# module.net
KiCad netlist of a schematic drawn in EAGLE
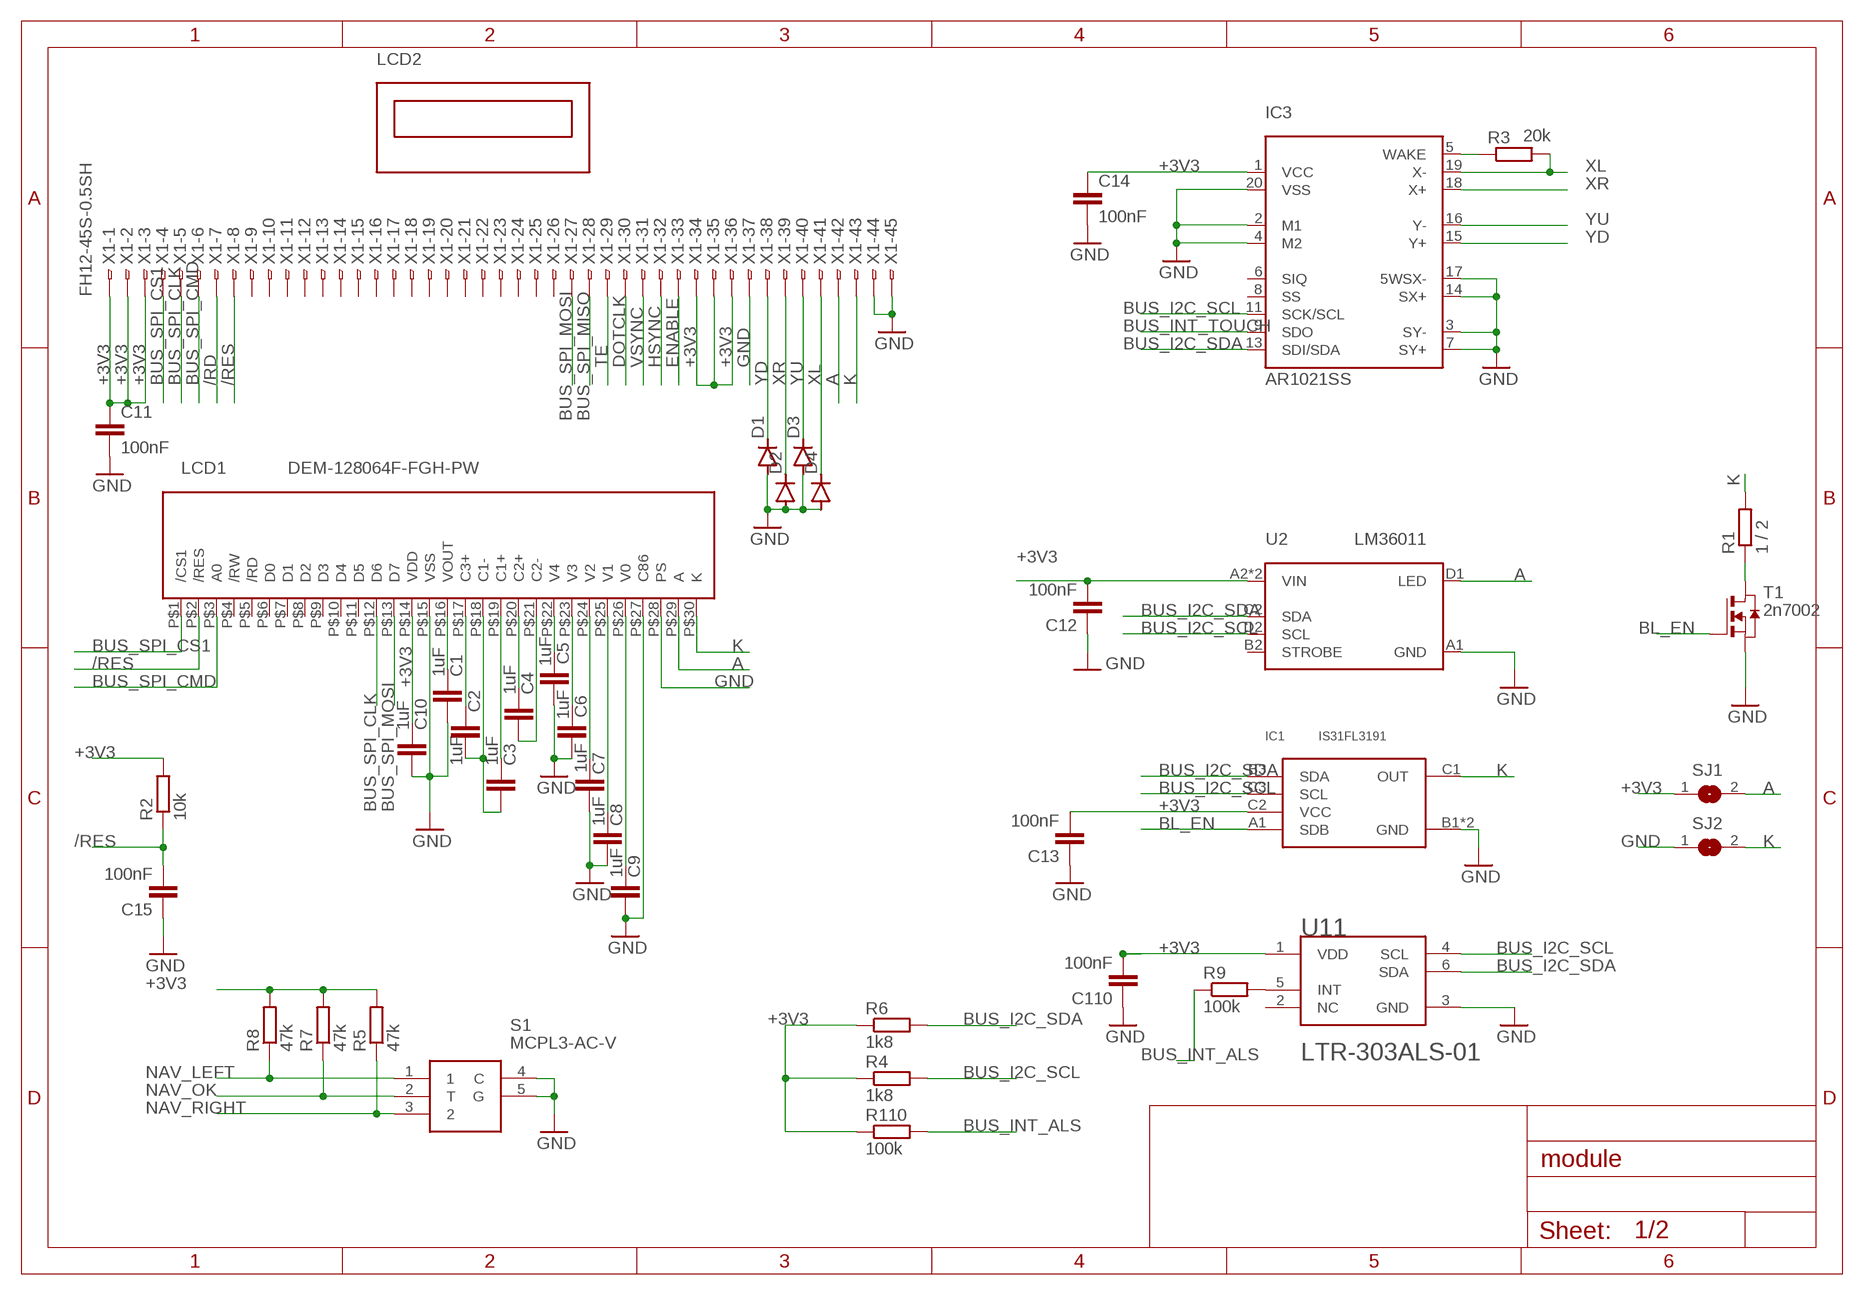
[diagram p0: schematic, sheet 1]
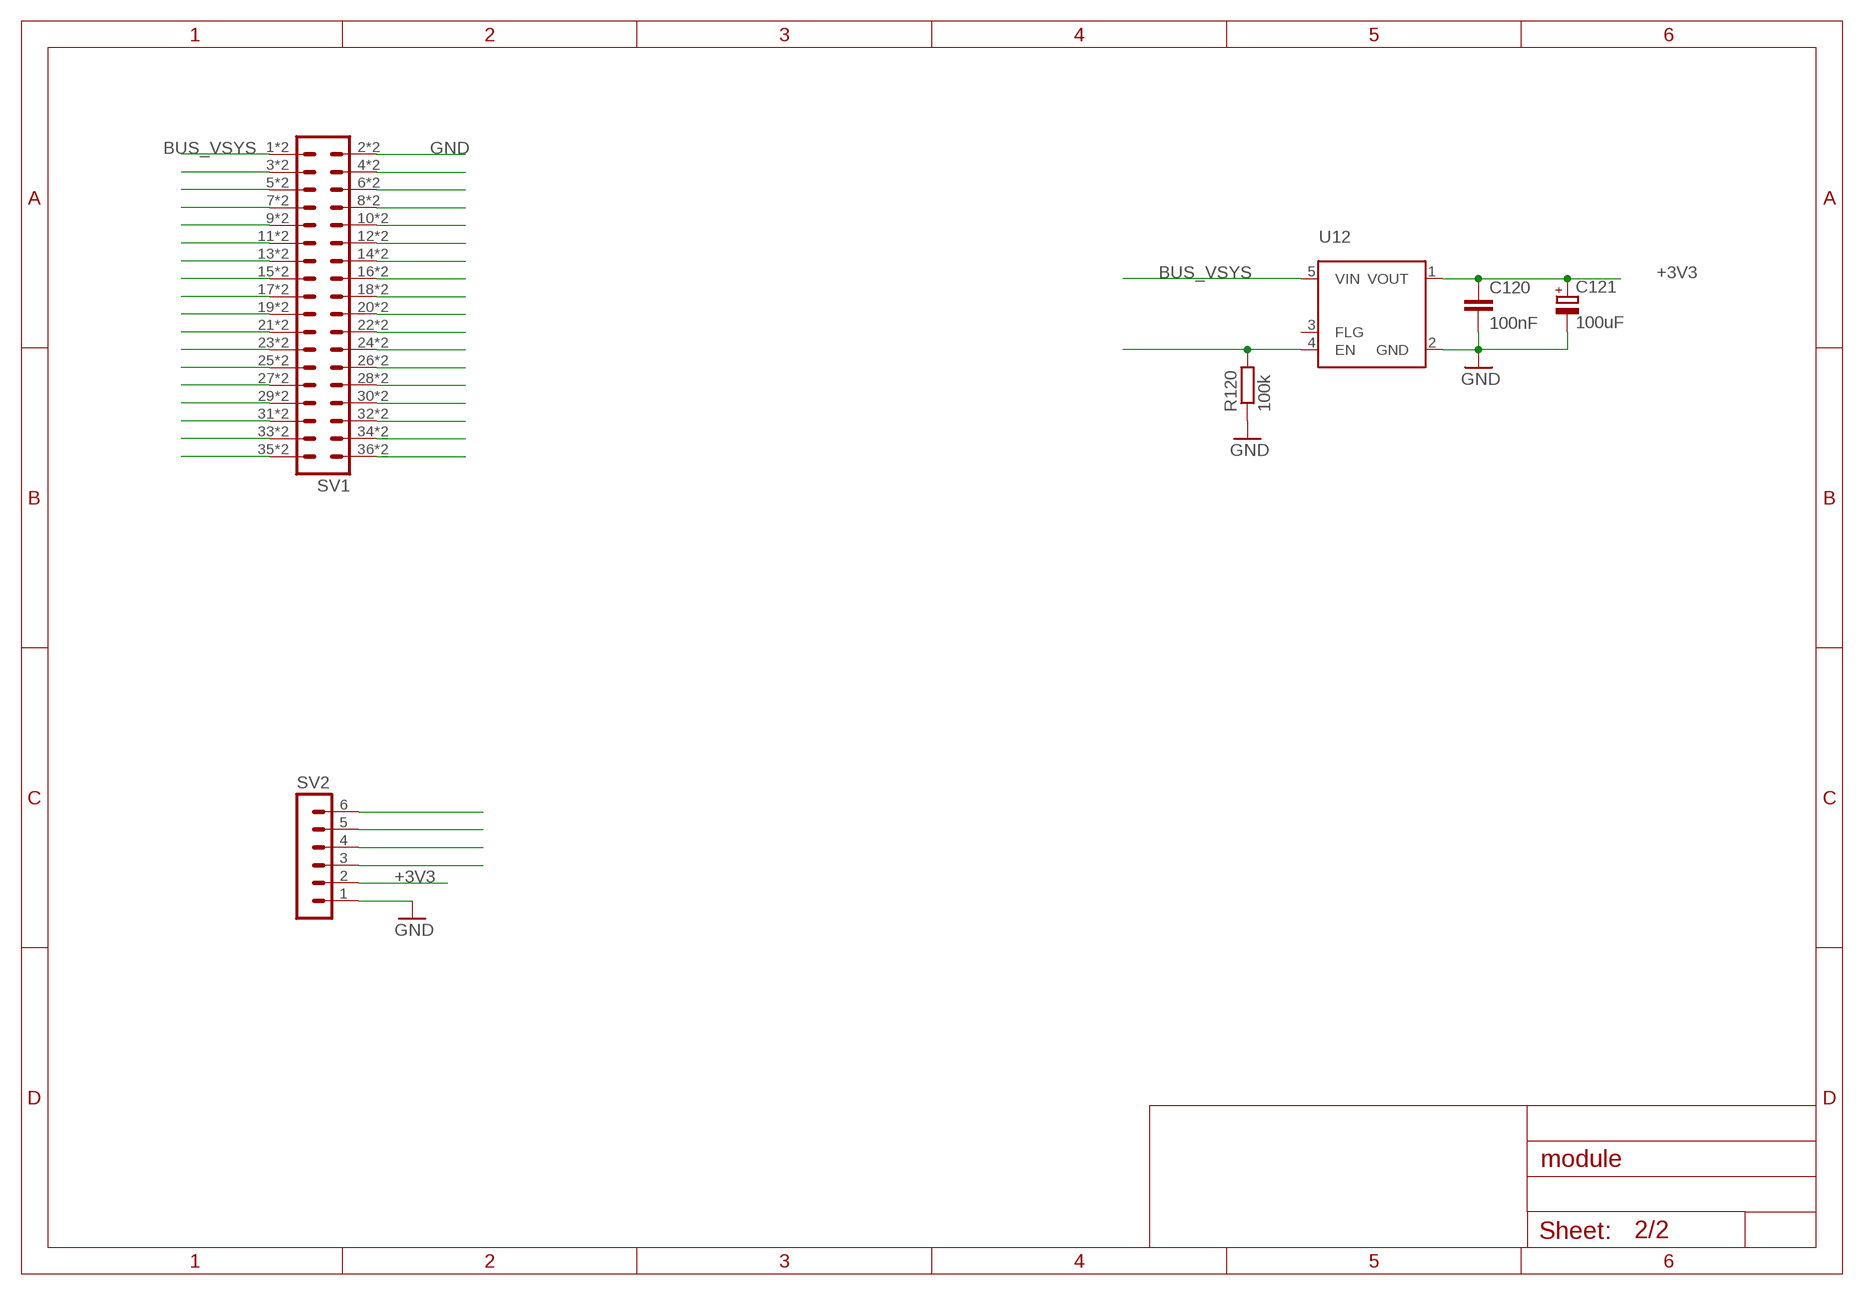
[diagram p1: schematic, sheet 2]

(export (version "E")
  (design (tool "Eeschema 10.0.6"))
  (components
    (comp (ref "C120")
      (value "100nF")
      (footprint "eagle-import:C0402")
      (libsource (lib "eagle-import") (part "C-EUC0402"))
    )
    (comp (ref "C121")
      (value "100uF")
      (footprint "eagle-import:SMC_C")
      (libsource (lib "eagle-import") (part "CPOL-EUSMCC"))
    )
    (comp (ref "R120")
      (value "100k")
      (footprint "eagle-import:R0402")
      (libsource (lib "eagle-import") (part "R-EU_R0402"))
    )
    (comp (ref "SV1")
      (value "MA18-2SMT")
      (footprint "eagle-import:MA18-2-SMT")
      (libsource (lib "eagle-import") (part "MA18-2SMT"))
    )
    (comp (ref "SV2")
      (value "CONN-1X6")
      (footprint "eagle-import:MA06-1")
      (libsource (lib "eagle-import") (part "CONN-1X6"))
    )
    (comp (ref "U12")
      (value "AP22802")
      (footprint "eagle-import:SOT25")
      (libsource (lib "eagle-import") (part "AP22802"))
    )
    (comp (ref "C1")
      (value "1uF")
      (footprint "eagle-import:C0805")
      (libsource (lib "eagle-import") (part "C-EUC0805"))
    )
    (comp (ref "C2")
      (value "1uF")
      (footprint "eagle-import:C0805")
      (libsource (lib "eagle-import") (part "C-EUC0805"))
    )
    (comp (ref "C3")
      (value "1uF")
      (footprint "eagle-import:C0805")
      (libsource (lib "eagle-import") (part "C-EUC0805"))
    )
    (comp (ref "C4")
      (value "1uF")
      (footprint "eagle-import:C0805")
      (libsource (lib "eagle-import") (part "C-EUC0805"))
    )
    (comp (ref "C5")
      (value "1uF")
      (footprint "eagle-import:C0805")
      (libsource (lib "eagle-import") (part "C-EUC0805"))
    )
    (comp (ref "C6")
      (value "1uF")
      (footprint "eagle-import:C0805")
      (libsource (lib "eagle-import") (part "C-EUC0805"))
    )
    (comp (ref "C7")
      (value "1uF")
      (footprint "eagle-import:C0805")
      (libsource (lib "eagle-import") (part "C-EUC0805"))
    )
    (comp (ref "C8")
      (value "1uF")
      (footprint "eagle-import:C0805")
      (libsource (lib "eagle-import") (part "C-EUC0805"))
    )
    (comp (ref "C9")
      (value "1uF")
      (footprint "eagle-import:C0805")
      (libsource (lib "eagle-import") (part "C-EUC0805"))
    )
    (comp (ref "C10")
      (value "1uF")
      (footprint "eagle-import:C0805")
      (libsource (lib "eagle-import") (part "C-EUC0805"))
    )
    (comp (ref "C11")
      (value "100nF")
      (footprint "eagle-import:C0603")
      (libsource (lib "eagle-import") (part "C-EUC0603"))
    )
    (comp (ref "C12")
      (value "100nF")
      (footprint "eagle-import:C0603")
      (libsource (lib "eagle-import") (part "C-EUC0603"))
    )
    (comp (ref "C13")
      (value "100nF")
      (footprint "eagle-import:C0603")
      (libsource (lib "eagle-import") (part "C-EUC0603"))
    )
    (comp (ref "C14")
      (value "100nF")
      (footprint "eagle-import:C0603")
      (libsource (lib "eagle-import") (part "C-EUC0603"))
    )
    (comp (ref "C15")
      (value "100nF")
      (footprint "eagle-import:C0603")
      (libsource (lib "eagle-import") (part "C-EUC0603"))
    )
    (comp (ref "C110")
      (value "100nF")
      (footprint "eagle-import:C0603")
      (libsource (lib "eagle-import") (part "C-EUC0603"))
    )
    (comp (ref "D1")
      (value "DIODE-SOD323-R")
      (footprint "eagle-import:SOD323-R")
      (libsource (lib "eagle-import") (part "DIODE-SOD323-R"))
    )
    (comp (ref "D2")
      (value "DIODE-SOD323-R")
      (footprint "eagle-import:SOD323-R")
      (libsource (lib "eagle-import") (part "DIODE-SOD323-R"))
    )
    (comp (ref "D3")
      (value "DIODE-SOD323-R")
      (footprint "eagle-import:SOD323-R")
      (libsource (lib "eagle-import") (part "DIODE-SOD323-R"))
    )
    (comp (ref "D4")
      (value "DIODE-SOD323-R")
      (footprint "eagle-import:SOD323-R")
      (libsource (lib "eagle-import") (part "DIODE-SOD323-R"))
    )
    (comp (ref "IC1")
      (value "IS31FL3191")
      (footprint "eagle-import:BGA9N40P3X3_133X133X56N")
      (libsource (lib "eagle-import") (part "IS31FL3191"))
    )
    (comp (ref "IC3")
      (value "AR1021SS")
      (footprint "eagle-import:SOP65P780X200-20N")
      (libsource (lib "eagle-import") (part "AR1021SS"))
    )
    (comp (ref "LCD1")
      (value "DEM-128064F-FGH-PW")
      (footprint "eagle-import:DEM128064FFGH")
      (libsource (lib "eagle-import") (part "DEM-128064F-FGH-PW"))
    )
    (comp (ref "LCD2")
      (value "DEM-230320K-TMH-PW")
      (footprint "eagle-import:DEM-240320K-TMH")
      (libsource (lib "eagle-import") (part "DEM-230320K-TMH-PW"))
    )
    (comp (ref "R1")
      (value "1 / 2")
      (footprint "eagle-import:R0603")
      (libsource (lib "eagle-import") (part "R-EU_R0603"))
    )
    (comp (ref "R2")
      (value "10k")
      (footprint "eagle-import:R0603")
      (libsource (lib "eagle-import") (part "R-EU_R0603"))
    )
    (comp (ref "R3")
      (value "20k")
      (footprint "eagle-import:R0603")
      (libsource (lib "eagle-import") (part "R-EU_R0603"))
    )
    (comp (ref "R4")
      (value "1k8")
      (footprint "eagle-import:R0603")
      (libsource (lib "eagle-import") (part "R-EU_R0603"))
    )
    (comp (ref "R5")
      (value "47k")
      (footprint "eagle-import:R0603")
      (libsource (lib "eagle-import") (part "R-EU_R0603"))
    )
    (comp (ref "R6")
      (value "1k8")
      (footprint "eagle-import:R0603")
      (libsource (lib "eagle-import") (part "R-EU_R0603"))
    )
    (comp (ref "R7")
      (value "47k")
      (footprint "eagle-import:R0603")
      (libsource (lib "eagle-import") (part "R-EU_R0603"))
    )
    (comp (ref "R8")
      (value "47k")
      (footprint "eagle-import:R0603")
      (libsource (lib "eagle-import") (part "R-EU_R0603"))
    )
    (comp (ref "R9")
      (value "100k")
      (footprint "eagle-import:R0603")
      (libsource (lib "eagle-import") (part "R-EU_R0603"))
    )
    (comp (ref "R110")
      (value "100k")
      (footprint "eagle-import:R0603")
      (libsource (lib "eagle-import") (part "R-EU_R0603"))
    )
    (comp (ref "S1")
      (value "MCPL3-AC-V")
      (footprint "eagle-import:MCPL3-AC-V")
      (libsource (lib "eagle-import") (part "MCPL3-AC-V"))
    )
    (comp (ref "SJ1") (value "SJ") (footprint "eagle-import:SJ") (libsource (lib "eagle-import") (part "SJ")))
    (comp (ref "SJ2") (value "SJ") (footprint "eagle-import:SJ") (libsource (lib "eagle-import") (part "SJ")))
    (comp (ref "T1")
      (value "2n7002")
      (footprint "eagle-import:SOT-23")
      (libsource (lib "eagle-import") (part "NMOSSOT23"))
    )
    (comp (ref "U2")
      (value "LM36011")
      (footprint "eagle-import:BGA8C35P2X4_151X80X50")
      (libsource (lib "eagle-import") (part "LM36011"))
    )
    (comp (ref "U11")
      (value "LITE-ON_LTR-303ALS-01LITE-ON_LTR-303ALS-01_0_0")
      (footprint "eagle-import:LITE-ON_LTR-303ALS-01_0")
      (fields
        (field (name "DIGIKEY_PART_NUMBER") "160-2161-1-ND")
        (field (name "MF") "Lite-On")
        (field (name "MOUSER_PART_NUMBER") "859-LTR-303ALS-01")
      )
      (libsource (lib "eagle-import") (part "LITE-ON_LTR-303ALS-01LITE-ON_LTR-303ALS-01_0_0"))
    )
    (comp (ref "X1")
      (value "FH12-45S-0.5SH")
      (footprint "eagle-import:FH12-45S-0.5SH")
      (libsource (lib "eagle-import") (part "FH12-45S-0.5SH"))
    )
  )
  (nets
    (net (code "1") (name "+3V3") (class "Default")
      (node (ref "C10") (pin "1") (pinfunction "1_1") (pintype "passive"))
      (node (ref "C11") (pin "1") (pinfunction "1_1") (pintype "passive"))
      (node (ref "C110") (pin "2") (pinfunction "2_2") (pintype "passive"))
      (node (ref "C12") (pin "2") (pinfunction "2_2") (pintype "passive"))
      (node (ref "C120") (pin "1") (pinfunction "1_1") (pintype "passive"))
      (node (ref "C121") (pin "+") (pinfunction "+_+") (pintype "passive"))
      (node (ref "C13") (pin "2") (pinfunction "2_2") (pintype "passive"))
      (node (ref "C14") (pin "1") (pinfunction "1_1") (pintype "passive"))
      (node (ref "IC1") (pin "C2") (pinfunction "VCC_C2") (pintype "bidirectional"))
      (node (ref "IC3") (pin "1") (pinfunction "VCC_1") (pintype "bidirectional"))
      (node (ref "LCD1") (pin "P$14") (pinfunction "VDD_P$14") (pintype "bidirectional"))
      (node (ref "R110") (pin "1") (pinfunction "1_1") (pintype "passive"))
      (node (ref "R2") (pin "2") (pinfunction "2_2") (pintype "passive"))
      (node (ref "R4") (pin "1") (pinfunction "1_1") (pintype "passive"))
      (node (ref "R5") (pin "2") (pinfunction "2_2") (pintype "passive"))
      (node (ref "R6") (pin "1") (pinfunction "1_1") (pintype "passive"))
      (node (ref "R7") (pin "2") (pinfunction "2_2") (pintype "passive"))
      (node (ref "R8") (pin "2") (pinfunction "2_2") (pintype "passive"))
      (node (ref "SJ1") (pin "1") (pinfunction "1_1") (pintype "passive"))
      (node (ref "SV2") (pin "2") (pinfunction "2_2") (pintype "passive"))
      (node (ref "U11") (pin "1") (pinfunction "VDD_1") (pintype "bidirectional"))
      (node (ref "U12") (pin "1") (pinfunction "VOUT_1") (pintype "bidirectional"))
      (node (ref "U2") (pin "A2") (pinfunction "VIN_A2") (pintype "bidirectional"))
      (node (ref "U2") (pin "C1") (pinfunction "VIN_C1") (pintype "bidirectional"))
      (node (ref "X1") (pin "1") (pinfunction "1_1") (pintype "passive"))
      (node (ref "X1") (pin "2") (pinfunction "1_2") (pintype "passive"))
      (node (ref "X1") (pin "3") (pinfunction "1_3") (pintype "passive"))
      (node (ref "X1") (pin "34") (pinfunction "1_34") (pintype "passive"))
      (node (ref "X1") (pin "35") (pinfunction "1_35") (pintype "passive"))
      (node (ref "X1") (pin "36") (pinfunction "1_36") (pintype "passive"))
    )
    (net (code "2") (name "A") (class "Default")
      (node (ref "LCD1") (pin "P$29") (pinfunction "A_P$29") (pintype "bidirectional"))
      (node (ref "SJ1") (pin "2") (pinfunction "2_2") (pintype "passive"))
      (node (ref "U2") (pin "D1") (pinfunction "LED_D1") (pintype "bidirectional"))
      (node (ref "X1") (pin "42") (pinfunction "1_42") (pintype "passive"))
    )
    (net (code "3") (name "BL_EN") (class "Default")
      (node (ref "IC1") (pin "A1") (pinfunction "SDB_A1") (pintype "bidirectional"))
      (node (ref "T1") (pin "3") (pinfunction "G_3") (pintype "passive"))
    )
    (net (code "4") (name "BUS_I2C_SCL") (class "Default")
      (node (ref "IC1") (pin "C3") (pinfunction "SCL_C3") (pintype "bidirectional"))
      (node (ref "IC3") (pin "11") (pinfunction "SCK/SCL_11") (pintype "bidirectional"))
      (node (ref "R4") (pin "2") (pinfunction "2_2") (pintype "passive"))
      (node (ref "U11") (pin "4") (pinfunction "SCL_4") (pintype "bidirectional"))
      (node (ref "U2") (pin "D2") (pinfunction "SCL_D2") (pintype "bidirectional"))
    )
    (net (code "5") (name "BUS_I2C_SDA") (class "Default")
      (node (ref "IC1") (pin "B3") (pinfunction "SDA_B3") (pintype "bidirectional"))
      (node (ref "IC3") (pin "13") (pinfunction "SDI/SDA_13") (pintype "bidirectional"))
      (node (ref "R6") (pin "2") (pinfunction "2_2") (pintype "passive"))
      (node (ref "U11") (pin "6") (pinfunction "SDA_6") (pintype "bidirectional"))
      (node (ref "U2") (pin "C2") (pinfunction "SDA_C2") (pintype "bidirectional"))
    )
    (net (code "6") (name "BUS_INT_ALS") (class "Default")
      (node (ref "R110") (pin "2") (pinfunction "2_2") (pintype "passive"))
      (node (ref "R9") (pin "1") (pinfunction "1_1") (pintype "passive"))
    )
    (net (code "7") (name "BUS_INT_TOUCH") (class "Default")
      (node (ref "IC3") (pin "9") (pinfunction "SDO_9") (pintype "bidirectional"))
    )
    (net (code "8") (name "BUS_SPI_CLK") (class "Default")
      (node (ref "LCD1") (pin "P$12") (pinfunction "D6_P$12") (pintype "bidirectional"))
      (node (ref "X1") (pin "5") (pinfunction "1_5") (pintype "passive"))
    )
    (net (code "9") (name "BUS_SPI_CMD") (class "Default")
      (node (ref "LCD1") (pin "P$3") (pinfunction "A0_P$3") (pintype "bidirectional"))
      (node (ref "X1") (pin "6") (pinfunction "1_6") (pintype "passive"))
    )
    (net (code "10") (name "BUS_SPI_CS1") (class "Default")
      (node (ref "LCD1") (pin "P$1") (pinfunction "/CS1_P$1") (pintype "bidirectional"))
      (node (ref "X1") (pin "4") (pinfunction "1_4") (pintype "passive"))
    )
    (net (code "11") (name "BUS_SPI_MISO") (class "Default")
      (node (ref "X1") (pin "28") (pinfunction "1_28") (pintype "passive"))
    )
    (net (code "12") (name "BUS_SPI_MOSI") (class "Default")
      (node (ref "LCD1") (pin "P$13") (pinfunction "D7_P$13") (pintype "bidirectional"))
      (node (ref "X1") (pin "27") (pinfunction "1_27") (pintype "passive"))
    )
    (net (code "13") (name "BUS_VSYS") (class "Default")
      (node (ref "SV1") (pin "1") (pinfunction "1_1") (pintype "passive"))
      (node (ref "SV1") (pin "P$1") (pinfunction "1_P$1") (pintype "passive"))
      (node (ref "U12") (pin "5") (pinfunction "VIN_5") (pintype "bidirectional"))
    )
    (net (code "14") (name "DOTCLK") (class "Default")
      (node (ref "X1") (pin "30") (pinfunction "1_30") (pintype "passive"))
    )
    (net (code "15") (name "ENABLE") (class "Default")
      (node (ref "X1") (pin "33") (pinfunction "1_33") (pintype "passive"))
    )
    (net (code "16") (name "GND") (class "Default")
      (node (ref "C1") (pin "2") (pinfunction "2_2") (pintype "passive"))
      (node (ref "C10") (pin "2") (pinfunction "2_2") (pintype "passive"))
      (node (ref "C11") (pin "2") (pinfunction "2_2") (pintype "passive"))
      (node (ref "C110") (pin "1") (pinfunction "1_1") (pintype "passive"))
      (node (ref "C12") (pin "1") (pinfunction "1_1") (pintype "passive"))
      (node (ref "C120") (pin "2") (pinfunction "2_2") (pintype "passive"))
      (node (ref "C121") (pin "-") (pinfunction "-_-") (pintype "passive"))
      (node (ref "C13") (pin "1") (pinfunction "1_1") (pintype "passive"))
      (node (ref "C14") (pin "2") (pinfunction "2_2") (pintype "passive"))
      (node (ref "C15") (pin "1") (pinfunction "1_1") (pintype "passive"))
      (node (ref "C5") (pin "2") (pinfunction "2_2") (pintype "passive"))
      (node (ref "C6") (pin "2") (pinfunction "2_2") (pintype "passive"))
      (node (ref "C7") (pin "2") (pinfunction "2_2") (pintype "passive"))
      (node (ref "C8") (pin "2") (pinfunction "2_2") (pintype "passive"))
      (node (ref "C9") (pin "2") (pinfunction "2_2") (pintype "passive"))
      (node (ref "D1") (pin "A") (pinfunction "A_A") (pintype "passive"))
      (node (ref "D2") (pin "A") (pinfunction "A_A") (pintype "passive"))
      (node (ref "D3") (pin "A") (pinfunction "A_A") (pintype "passive"))
      (node (ref "D4") (pin "A") (pinfunction "A_A") (pintype "passive"))
      (node (ref "IC1") (pin "B1") (pinfunction "GND_B1") (pintype "bidirectional"))
      (node (ref "IC1") (pin "B2") (pinfunction "GND_B2") (pintype "bidirectional"))
      (node (ref "IC3") (pin "14") (pinfunction "SX+_14") (pintype "bidirectional"))
      (node (ref "IC3") (pin "17") (pinfunction "5WSX-_17") (pintype "bidirectional"))
      (node (ref "IC3") (pin "2") (pinfunction "M1_2") (pintype "bidirectional"))
      (node (ref "IC3") (pin "20") (pinfunction "VSS_20") (pintype "bidirectional"))
      (node (ref "IC3") (pin "3") (pinfunction "SY-_3") (pintype "bidirectional"))
      (node (ref "IC3") (pin "4") (pinfunction "M2_4") (pintype "bidirectional"))
      (node (ref "IC3") (pin "7") (pinfunction "SY+_7") (pintype "bidirectional"))
      (node (ref "LCD1") (pin "P$15") (pinfunction "VSS_P$15") (pintype "bidirectional"))
      (node (ref "LCD1") (pin "P$27") (pinfunction "C86_P$27") (pintype "bidirectional"))
      (node (ref "LCD1") (pin "P$28") (pinfunction "PS_P$28") (pintype "bidirectional"))
      (node (ref "R120") (pin "1") (pinfunction "1_1") (pintype "passive"))
      (node (ref "S1") (pin "4") (pinfunction "C_4") (pintype "bidirectional"))
      (node (ref "S1") (pin "5") (pinfunction "G_5") (pintype "bidirectional"))
      (node (ref "SJ2") (pin "1") (pinfunction "1_1") (pintype "passive"))
      (node (ref "SV1") (pin "2") (pinfunction "2_2") (pintype "passive"))
      (node (ref "SV1") (pin "P$2") (pinfunction "2_P$2") (pintype "passive"))
      (node (ref "SV2") (pin "1") (pinfunction "1_1") (pintype "passive"))
      (node (ref "T1") (pin "2") (pinfunction "S_2") (pintype "passive"))
      (node (ref "U11") (pin "3") (pinfunction "GND_3") (pintype "bidirectional"))
      (node (ref "U12") (pin "2") (pinfunction "GND_2") (pintype "bidirectional"))
      (node (ref "U2") (pin "A1") (pinfunction "GND_A1") (pintype "bidirectional"))
      (node (ref "X1") (pin "37") (pinfunction "1_37") (pintype "passive"))
      (node (ref "X1") (pin "44") (pinfunction "1_44") (pintype "passive"))
      (node (ref "X1") (pin "45") (pinfunction "1_45") (pintype "passive"))
    )
    (net (code "17") (name "HSYNC") (class "Default")
      (node (ref "X1") (pin "32") (pinfunction "1_32") (pintype "passive"))
    )
    (net (code "18") (name "K") (class "Default")
      (node (ref "IC1") (pin "C1") (pinfunction "OUT_C1") (pintype "bidirectional"))
      (node (ref "LCD1") (pin "P$30") (pinfunction "K_P$30") (pintype "bidirectional"))
      (node (ref "R1") (pin "2") (pinfunction "2_2") (pintype "passive"))
      (node (ref "SJ2") (pin "2") (pinfunction "2_2") (pintype "passive"))
      (node (ref "X1") (pin "43") (pinfunction "1_43") (pintype "passive"))
    )
    (net (code "19") (name "NAV_LEFT") (class "Default")
      (node (ref "R8") (pin "1") (pinfunction "1_1") (pintype "passive"))
      (node (ref "S1") (pin "1") (pinfunction "1_1") (pintype "bidirectional"))
    )
    (net (code "20") (name "NAV_OK") (class "Default")
      (node (ref "R7") (pin "1") (pinfunction "1_1") (pintype "passive"))
      (node (ref "S1") (pin "2") (pinfunction "T_2") (pintype "bidirectional"))
    )
    (net (code "21") (name "NAV_RIGHT") (class "Default")
      (node (ref "R5") (pin "1") (pinfunction "1_1") (pintype "passive"))
      (node (ref "S1") (pin "3") (pinfunction "2_3") (pintype "bidirectional"))
    )
    (net (code "22") (name "Net-(IC3-WAKE)") (class "Default")
      (node (ref "IC3") (pin "5") (pinfunction "WAKE_5") (pintype "bidirectional"))
      (node (ref "R3") (pin "1") (pinfunction "1_1") (pintype "passive"))
    )
    (net (code "23") (name "Net-(LCD1-C1+)") (class "Default")
      (node (ref "C3") (pin "1") (pinfunction "1_1") (pintype "passive"))
      (node (ref "LCD1") (pin "P$19") (pinfunction "C1+_P$19") (pintype "bidirectional"))
    )
    (net (code "24") (name "Net-(LCD1-C1-)") (class "Default")
      (node (ref "C2") (pin "2") (pinfunction "2_2") (pintype "passive"))
      (node (ref "C3") (pin "2") (pinfunction "2_2") (pintype "passive"))
      (node (ref "LCD1") (pin "P$18") (pinfunction "C1-_P$18") (pintype "bidirectional"))
    )
    (net (code "25") (name "Net-(LCD1-C2+)") (class "Default")
      (node (ref "C4") (pin "1") (pinfunction "1_1") (pintype "passive"))
      (node (ref "LCD1") (pin "P$20") (pinfunction "C2+_P$20") (pintype "bidirectional"))
    )
    (net (code "26") (name "Net-(LCD1-C2-)") (class "Default")
      (node (ref "C4") (pin "2") (pinfunction "2_2") (pintype "passive"))
      (node (ref "LCD1") (pin "P$21") (pinfunction "C2-_P$21") (pintype "bidirectional"))
    )
    (net (code "27") (name "Net-(LCD1-C3+)") (class "Default")
      (node (ref "C2") (pin "1") (pinfunction "1_1") (pintype "passive"))
      (node (ref "LCD1") (pin "P$17") (pinfunction "C3+_P$17") (pintype "bidirectional"))
    )
    (net (code "28") (name "Net-(LCD1-V0)") (class "Default")
      (node (ref "C9") (pin "1") (pinfunction "1_1") (pintype "passive"))
      (node (ref "LCD1") (pin "P$26") (pinfunction "V0_P$26") (pintype "bidirectional"))
    )
    (net (code "29") (name "Net-(LCD1-V1)") (class "Default")
      (node (ref "C8") (pin "1") (pinfunction "1_1") (pintype "passive"))
      (node (ref "LCD1") (pin "P$25") (pinfunction "V1_P$25") (pintype "bidirectional"))
    )
    (net (code "30") (name "Net-(LCD1-V2)") (class "Default")
      (node (ref "C7") (pin "1") (pinfunction "1_1") (pintype "passive"))
      (node (ref "LCD1") (pin "P$24") (pinfunction "V2_P$24") (pintype "bidirectional"))
    )
    (net (code "31") (name "Net-(LCD1-V3)") (class "Default")
      (node (ref "C6") (pin "1") (pinfunction "1_1") (pintype "passive"))
      (node (ref "LCD1") (pin "P$23") (pinfunction "V3_P$23") (pintype "bidirectional"))
    )
    (net (code "32") (name "Net-(LCD1-V4)") (class "Default")
      (node (ref "C5") (pin "1") (pinfunction "1_1") (pintype "passive"))
      (node (ref "LCD1") (pin "P$22") (pinfunction "V4_P$22") (pintype "bidirectional"))
    )
    (net (code "33") (name "Net-(LCD1-VOUT)") (class "Default")
      (node (ref "C1") (pin "1") (pinfunction "1_1") (pintype "passive"))
      (node (ref "LCD1") (pin "P$16") (pinfunction "VOUT_P$16") (pintype "bidirectional"))
    )
    (net (code "34") (name "Net-(SV1-3-PadP$3)") (class "Default")
      (node (ref "SV1") (pin "3") (pinfunction "3_3") (pintype "passive"))
      (node (ref "SV1") (pin "P$3") (pinfunction "3_P$3") (pintype "passive"))
    )
    (net (code "35") (name "Net-(SV1-4-PadP$4)") (class "Default")
      (node (ref "SV1") (pin "4") (pinfunction "4_4") (pintype "passive"))
      (node (ref "SV1") (pin "P$4") (pinfunction "4_P$4") (pintype "passive"))
    )
    (net (code "36") (name "Net-(SV1-5-PadP$5)") (class "Default")
      (node (ref "SV1") (pin "5") (pinfunction "5_5") (pintype "passive"))
      (node (ref "SV1") (pin "P$5") (pinfunction "5_P$5") (pintype "passive"))
    )
    (net (code "37") (name "Net-(SV1-6-PadP$6)") (class "Default")
      (node (ref "SV1") (pin "6") (pinfunction "6_6") (pintype "passive"))
      (node (ref "SV1") (pin "P$6") (pinfunction "6_P$6") (pintype "passive"))
    )
    (net (code "38") (name "Net-(SV1-7-PadP$7)") (class "Default")
      (node (ref "SV1") (pin "7") (pinfunction "7_7") (pintype "passive"))
      (node (ref "SV1") (pin "P$7") (pinfunction "7_P$7") (pintype "passive"))
    )
    (net (code "39") (name "Net-(SV1-8-PadP$8)") (class "Default")
      (node (ref "SV1") (pin "8") (pinfunction "8_8") (pintype "passive"))
      (node (ref "SV1") (pin "P$8") (pinfunction "8_P$8") (pintype "passive"))
    )
    (net (code "40") (name "Net-(SV1-9-PadP$9)") (class "Default")
      (node (ref "SV1") (pin "9") (pinfunction "9_9") (pintype "passive"))
      (node (ref "SV1") (pin "P$9") (pinfunction "9_P$9") (pintype "passive"))
    )
    (net (code "41") (name "Net-(SV1-10-PadP$10)") (class "Default")
      (node (ref "SV1") (pin "10") (pinfunction "10_10") (pintype "passive"))
      (node (ref "SV1") (pin "P$10") (pinfunction "10_P$10") (pintype "passive"))
    )
    (net (code "42") (name "Net-(SV1-11-PadP$11)") (class "Default")
      (node (ref "SV1") (pin "11") (pinfunction "11_11") (pintype "passive"))
      (node (ref "SV1") (pin "P$11") (pinfunction "11_P$11") (pintype "passive"))
    )
    (net (code "43") (name "Net-(SV1-12-PadP$12)") (class "Default")
      (node (ref "SV1") (pin "12") (pinfunction "12_12") (pintype "passive"))
      (node (ref "SV1") (pin "P$12") (pinfunction "12_P$12") (pintype "passive"))
    )
    (net (code "44") (name "Net-(SV1-13-PadP$13)") (class "Default")
      (node (ref "SV1") (pin "13") (pinfunction "13_13") (pintype "passive"))
      (node (ref "SV1") (pin "P$13") (pinfunction "13_P$13") (pintype "passive"))
    )
    (net (code "45") (name "Net-(SV1-14-PadP$14)") (class "Default")
      (node (ref "SV1") (pin "14") (pinfunction "14_14") (pintype "passive"))
      (node (ref "SV1") (pin "P$14") (pinfunction "14_P$14") (pintype "passive"))
    )
    (net (code "46") (name "Net-(SV1-15-PadP$15)") (class "Default")
      (node (ref "SV1") (pin "15") (pinfunction "15_15") (pintype "passive"))
      (node (ref "SV1") (pin "P$15") (pinfunction "15_P$15") (pintype "passive"))
    )
    (net (code "47") (name "Net-(SV1-16-PadP$16)") (class "Default")
      (node (ref "SV1") (pin "16") (pinfunction "16_16") (pintype "passive"))
      (node (ref "SV1") (pin "P$16") (pinfunction "16_P$16") (pintype "passive"))
    )
    (net (code "48") (name "Net-(SV1-17-PadP$17)") (class "Default")
      (node (ref "SV1") (pin "17") (pinfunction "17_17") (pintype "passive"))
      (node (ref "SV1") (pin "P$17") (pinfunction "17_P$17") (pintype "passive"))
    )
    (net (code "49") (name "Net-(SV1-18-PadP$18)") (class "Default")
      (node (ref "SV1") (pin "18") (pinfunction "18_18") (pintype "passive"))
      (node (ref "SV1") (pin "P$18") (pinfunction "18_P$18") (pintype "passive"))
    )
    (net (code "50") (name "Net-(SV1-19-PadP$19)") (class "Default")
      (node (ref "SV1") (pin "19") (pinfunction "19_19") (pintype "passive"))
      (node (ref "SV1") (pin "P$19") (pinfunction "19_P$19") (pintype "passive"))
    )
    (net (code "51") (name "Net-(SV1-20-PadP$20)") (class "Default")
      (node (ref "SV1") (pin "20") (pinfunction "20_20") (pintype "passive"))
      (node (ref "SV1") (pin "P$20") (pinfunction "20_P$20") (pintype "passive"))
    )
    (net (code "52") (name "Net-(SV1-21-PadP$21)") (class "Default")
      (node (ref "SV1") (pin "21") (pinfunction "21_21") (pintype "passive"))
      (node (ref "SV1") (pin "P$21") (pinfunction "21_P$21") (pintype "passive"))
    )
    (net (code "53") (name "Net-(SV1-22-PadP$22)") (class "Default")
      (node (ref "SV1") (pin "22") (pinfunction "22_22") (pintype "passive"))
      (node (ref "SV1") (pin "P$22") (pinfunction "22_P$22") (pintype "passive"))
    )
    (net (code "54") (name "Net-(SV1-23-PadP$23)") (class "Default")
      (node (ref "SV1") (pin "23") (pinfunction "23_23") (pintype "passive"))
      (node (ref "SV1") (pin "P$23") (pinfunction "23_P$23") (pintype "passive"))
    )
    (net (code "55") (name "Net-(SV1-24-PadP$24)") (class "Default")
      (node (ref "SV1") (pin "24") (pinfunction "24_24") (pintype "passive"))
      (node (ref "SV1") (pin "P$24") (pinfunction "24_P$24") (pintype "passive"))
    )
    (net (code "56") (name "Net-(SV1-25-PadP$25)") (class "Default")
      (node (ref "SV1") (pin "25") (pinfunction "25_25") (pintype "passive"))
      (node (ref "SV1") (pin "P$25") (pinfunction "25_P$25") (pintype "passive"))
    )
    (net (code "57") (name "Net-(SV1-26-PadP$26)") (class "Default")
      (node (ref "SV1") (pin "26") (pinfunction "26_26") (pintype "passive"))
      (node (ref "SV1") (pin "P$26") (pinfunction "26_P$26") (pintype "passive"))
    )
    (net (code "58") (name "Net-(SV1-27-PadP$27)") (class "Default")
      (node (ref "SV1") (pin "27") (pinfunction "27_27") (pintype "passive"))
      (node (ref "SV1") (pin "P$27") (pinfunction "27_P$27") (pintype "passive"))
    )
    (net (code "59") (name "Net-(SV1-28-PadP$28)") (class "Default")
      (node (ref "SV1") (pin "28") (pinfunction "28_28") (pintype "passive"))
      (node (ref "SV1") (pin "P$28") (pinfunction "28_P$28") (pintype "passive"))
    )
    (net (code "60") (name "Net-(SV1-29-PadP$29)") (class "Default")
      (node (ref "SV1") (pin "29") (pinfunction "29_29") (pintype "passive"))
      (node (ref "SV1") (pin "P$29") (pinfunction "29_P$29") (pintype "passive"))
    )
    (net (code "61") (name "Net-(SV1-30-PadP$30)") (class "Default")
      (node (ref "SV1") (pin "30") (pinfunction "30_30") (pintype "passive"))
      (node (ref "SV1") (pin "P$30") (pinfunction "30_P$30") (pintype "passive"))
    )
    (net (code "62") (name "Net-(SV1-31-PadP$31)") (class "Default")
      (node (ref "SV1") (pin "31") (pinfunction "31_31") (pintype "passive"))
      (node (ref "SV1") (pin "P$31") (pinfunction "31_P$31") (pintype "passive"))
    )
    (net (code "63") (name "Net-(SV1-32-PadP$32)") (class "Default")
      (node (ref "SV1") (pin "32") (pinfunction "32_32") (pintype "passive"))
      (node (ref "SV1") (pin "P$32") (pinfunction "32_P$32") (pintype "passive"))
    )
    (net (code "64") (name "Net-(SV1-33-PadP$33)") (class "Default")
      (node (ref "SV1") (pin "33") (pinfunction "33_33") (pintype "passive"))
      (node (ref "SV1") (pin "P$33") (pinfunction "33_P$33") (pintype "passive"))
    )
    (net (code "65") (name "Net-(SV1-34-PadP$34)") (class "Default")
      (node (ref "SV1") (pin "34") (pinfunction "34_34") (pintype "passive"))
      (node (ref "SV1") (pin "P$34") (pinfunction "34_P$34") (pintype "passive"))
    )
    (net (code "66") (name "Net-(SV1-35-PadP$35)") (class "Default")
      (node (ref "SV1") (pin "35") (pinfunction "35_35") (pintype "passive"))
      (node (ref "SV1") (pin "P$35") (pinfunction "35_P$35") (pintype "passive"))
    )
    (net (code "67") (name "Net-(SV1-36-PadP$36)") (class "Default")
      (node (ref "SV1") (pin "36") (pinfunction "36_36") (pintype "passive"))
      (node (ref "SV1") (pin "P$36") (pinfunction "36_P$36") (pintype "passive"))
    )
    (net (code "68") (name "Net-(T1-D)") (class "Default")
      (node (ref "R1") (pin "1") (pinfunction "1_1") (pintype "passive"))
      (node (ref "T1") (pin "1") (pinfunction "D_1") (pintype "passive"))
    )
    (net (code "69") (name "Net-(U11-INT)") (class "Default")
      (node (ref "R9") (pin "2") (pinfunction "2_2") (pintype "passive"))
      (node (ref "U11") (pin "5") (pinfunction "INT_5") (pintype "bidirectional"))
    )
    (net (code "70") (name "Net-(U12-EN)") (class "Default")
      (node (ref "R120") (pin "2") (pinfunction "2_2") (pintype "passive"))
      (node (ref "U12") (pin "4") (pinfunction "EN_4") (pintype "bidirectional"))
    )
    (net (code "71") (name "TE") (class "Default")
      (node (ref "X1") (pin "29") (pinfunction "1_29") (pintype "passive"))
    )
    (net (code "72") (name "VSYNC") (class "Default")
      (node (ref "X1") (pin "31") (pinfunction "1_31") (pintype "passive"))
    )
    (net (code "73") (name "XL") (class "Default")
      (node (ref "D4") (pin "C") (pinfunction "C_C") (pintype "passive"))
      (node (ref "IC3") (pin "19") (pinfunction "X-_19") (pintype "bidirectional"))
      (node (ref "R3") (pin "2") (pinfunction "2_2") (pintype "passive"))
      (node (ref "X1") (pin "41") (pinfunction "1_41") (pintype "passive"))
    )
    (net (code "74") (name "XR") (class "Default")
      (node (ref "D2") (pin "C") (pinfunction "C_C") (pintype "passive"))
      (node (ref "IC3") (pin "18") (pinfunction "X+_18") (pintype "bidirectional"))
      (node (ref "X1") (pin "39") (pinfunction "1_39") (pintype "passive"))
    )
    (net (code "75") (name "YD") (class "Default")
      (node (ref "D1") (pin "C") (pinfunction "C_C") (pintype "passive"))
      (node (ref "IC3") (pin "15") (pinfunction "Y+_15") (pintype "bidirectional"))
      (node (ref "X1") (pin "38") (pinfunction "1_38") (pintype "passive"))
    )
    (net (code "76") (name "YU") (class "Default")
      (node (ref "D3") (pin "C") (pinfunction "C_C") (pintype "passive"))
      (node (ref "IC3") (pin "16") (pinfunction "Y-_16") (pintype "bidirectional"))
      (node (ref "X1") (pin "40") (pinfunction "1_40") (pintype "passive"))
    )
    (net (code "77") (name "unconnected-(IC3-SIQ-Pad6)") (class "Default")
      (node (ref "IC3") (pin "6") (pinfunction "SIQ_6") (pintype "bidirectional"))
    )
    (net (code "78") (name "unconnected-(IC3-SS-Pad8)") (class "Default")
      (node (ref "IC3") (pin "8") (pinfunction "SS_8") (pintype "bidirectional"))
    )
    (net (code "79") (name "unconnected-(LCD1-D0-PadP$6)") (class "Default")
      (node (ref "LCD1") (pin "P$6") (pinfunction "D0_P$6") (pintype "bidirectional"))
    )
    (net (code "80") (name "unconnected-(LCD1-D1-PadP$7)") (class "Default")
      (node (ref "LCD1") (pin "P$7") (pinfunction "D1_P$7") (pintype "bidirectional"))
    )
    (net (code "81") (name "unconnected-(LCD1-D2-PadP$8)") (class "Default")
      (node (ref "LCD1") (pin "P$8") (pinfunction "D2_P$8") (pintype "bidirectional"))
    )
    (net (code "82") (name "unconnected-(LCD1-D3-PadP$9)") (class "Default")
      (node (ref "LCD1") (pin "P$9") (pinfunction "D3_P$9") (pintype "bidirectional"))
    )
    (net (code "83") (name "unconnected-(LCD1-D4-PadP$10)") (class "Default")
      (node (ref "LCD1") (pin "P$10") (pinfunction "D4_P$10") (pintype "bidirectional"))
    )
    (net (code "84") (name "unconnected-(LCD1-D5-PadP$11)") (class "Default")
      (node (ref "LCD1") (pin "P$11") (pinfunction "D5_P$11") (pintype "bidirectional"))
    )
    (net (code "85") (name "unconnected-(LCD1-{slash}RD-PadP$5)") (class "Default")
      (node (ref "LCD1") (pin "P$5") (pinfunction "/RD_P$5") (pintype "bidirectional"))
    )
    (net (code "86") (name "unconnected-(LCD1-{slash}RW-PadP$4)") (class "Default")
      (node (ref "LCD1") (pin "P$4") (pinfunction "/RW_P$4") (pintype "bidirectional"))
    )
    (net (code "87") (name "unconnected-(SV2-Pad3)") (class "Default")
      (node (ref "SV2") (pin "3") (pinfunction "3_3") (pintype "passive"))
    )
    (net (code "88") (name "unconnected-(SV2-Pad4)") (class "Default")
      (node (ref "SV2") (pin "4") (pinfunction "4_4") (pintype "passive"))
    )
    (net (code "89") (name "unconnected-(SV2-Pad5)") (class "Default")
      (node (ref "SV2") (pin "5") (pinfunction "5_5") (pintype "passive"))
    )
    (net (code "90") (name "unconnected-(SV2-Pad6)") (class "Default")
      (node (ref "SV2") (pin "6") (pinfunction "6_6") (pintype "passive"))
    )
    (net (code "91") (name "unconnected-(U2-STROBE-PadB2)") (class "Default")
      (node (ref "U2") (pin "B2") (pinfunction "STROBE_B2") (pintype "bidirectional"))
    )
    (net (code "92") (name "unconnected-(U11-NC-Pad2)") (class "Default")
      (node (ref "U11") (pin "2") (pinfunction "NC_2") (pintype "bidirectional"))
    )
    (net (code "93") (name "unconnected-(U12-FLG-Pad3)") (class "Default")
      (node (ref "U12") (pin "3") (pinfunction "FLG_3") (pintype "bidirectional"))
    )
    (net (code "94") (name "unconnected-(X1AS-1-Pad9)") (class "Default")
      (node (ref "X1") (pin "9") (pinfunction "1_9") (pintype "passive"))
    )
    (net (code "95") (name "unconnected-(X1B-1-Pad10)") (class "Default")
      (node (ref "X1") (pin "10") (pinfunction "1_10") (pintype "passive"))
    )
    (net (code "96") (name "unconnected-(X1C-1-Pad11)") (class "Default")
      (node (ref "X1") (pin "11") (pinfunction "1_11") (pintype "passive"))
    )
    (net (code "97") (name "unconnected-(X1D-1-Pad12)") (class "Default")
      (node (ref "X1") (pin "12") (pinfunction "1_12") (pintype "passive"))
    )
    (net (code "98") (name "unconnected-(X1E-1-Pad13)") (class "Default")
      (node (ref "X1") (pin "13") (pinfunction "1_13") (pintype "passive"))
    )
    (net (code "99") (name "unconnected-(X1F-1-Pad14)") (class "Default")
      (node (ref "X1") (pin "14") (pinfunction "1_14") (pintype "passive"))
    )
    (net (code "100") (name "unconnected-(X1G-1-Pad15)") (class "Default")
      (node (ref "X1") (pin "15") (pinfunction "1_15") (pintype "passive"))
    )
    (net (code "101") (name "unconnected-(X1H-1-Pad16)") (class "Default")
      (node (ref "X1") (pin "16") (pinfunction "1_16") (pintype "passive"))
    )
    (net (code "102") (name "unconnected-(X1I-1-Pad17)") (class "Default")
      (node (ref "X1") (pin "17") (pinfunction "1_17") (pintype "passive"))
    )
    (net (code "103") (name "unconnected-(X1J-1-Pad18)") (class "Default")
      (node (ref "X1") (pin "18") (pinfunction "1_18") (pintype "passive"))
    )
    (net (code "104") (name "unconnected-(X1K-1-Pad19)") (class "Default")
      (node (ref "X1") (pin "19") (pinfunction "1_19") (pintype "passive"))
    )
    (net (code "105") (name "unconnected-(X1M-1-Pad20)") (class "Default")
      (node (ref "X1") (pin "20") (pinfunction "1_20") (pintype "passive"))
    )
    (net (code "106") (name "unconnected-(X1N-1-Pad21)") (class "Default")
      (node (ref "X1") (pin "21") (pinfunction "1_21") (pintype "passive"))
    )
    (net (code "107") (name "unconnected-(X1O-1-Pad22)") (class "Default")
      (node (ref "X1") (pin "22") (pinfunction "1_22") (pintype "passive"))
    )
    (net (code "108") (name "unconnected-(X1P-1-Pad23)") (class "Default")
      (node (ref "X1") (pin "23") (pinfunction "1_23") (pintype "passive"))
    )
    (net (code "109") (name "unconnected-(X1Q-1-Pad24)") (class "Default")
      (node (ref "X1") (pin "24") (pinfunction "1_24") (pintype "passive"))
    )
    (net (code "110") (name "unconnected-(X1R-1-Pad25)") (class "Default")
      (node (ref "X1") (pin "25") (pinfunction "1_25") (pintype "passive"))
    )
    (net (code "111") (name "unconnected-(X1S-1-Pad26)") (class "Default")
      (node (ref "X1") (pin "26") (pinfunction "1_26") (pintype "passive"))
    )
    (net (code "112") (name "{slash}RD") (class "Default")
      (node (ref "X1") (pin "7") (pinfunction "1_7") (pintype "passive"))
    )
    (net (code "113") (name "{slash}RES") (class "Default")
      (node (ref "C15") (pin "2") (pinfunction "2_2") (pintype "passive"))
      (node (ref "LCD1") (pin "P$2") (pinfunction "/RES_P$2") (pintype "bidirectional"))
      (node (ref "R2") (pin "1") (pinfunction "1_1") (pintype "passive"))
      (node (ref "X1") (pin "8") (pinfunction "1_8") (pintype "passive"))
    )
  )
)
